# DetectorOptode.net
KiCad netlist of a schematic drawn in Altium Designer
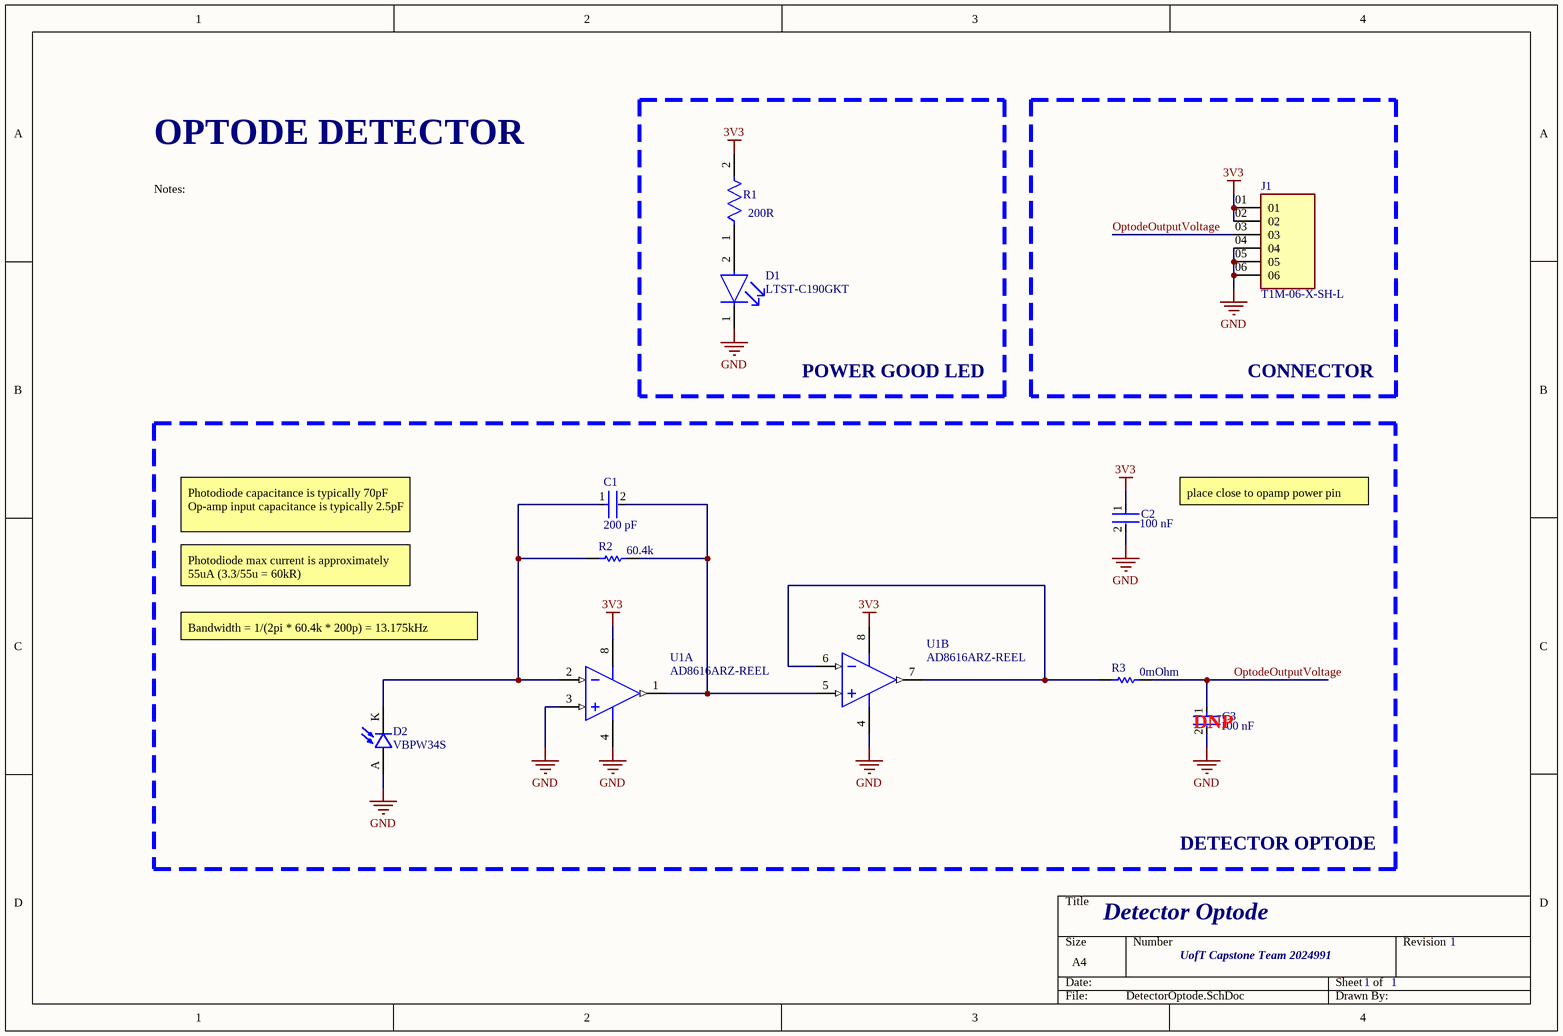
[diagram p0: DetectorOptode.SchDoc]

(export (version "E")
  (design (tool "Eeschema 10.0.6"))
  (components
    (comp (ref "C1")
      (value "C0603C201J5GACTU")
      (footprint "FP-C0603C-CF-MFG")
      (description "CAP CER 200PF 50V 5% NP0 0603")
      (fields
        (field (name "CAPACITANCE") "200 pF")
        (field (name "MANUFACTURER") "KEMET")
        (field (name "OCTOPART") "https://octopart.com/c0603c201j5gactu-kemet-9143917")
      )
      (libsource (lib "Altium Content Vault") (part "b4654b650e69147ec39a6b967a45e02"))
    )
    (comp (ref "C2")
      (value "CC0603KRX7R7BB104")
      (footprint "FP-CC0603-DA-MFG")
      (description "CAP CER 0.1UF 16V X7R 0603")
      (fields
        (field (name "OCTOPART") "https://octopart.com/cc0603krx7r7bb104-yageo-192941")
        (field (name "TOLERANCE") "0.1")
        (field (name "CAPACITANCE") "100 nF")
      )
      (libsource (lib "Altium Content Vault") (part "11868f565c42a9108669ba33697ecf6"))
    )
    (comp (ref "C3")
      (value "CC0603KRX7R7BB104")
      (footprint "FP-CC0603-DA-MFG")
      (description "CAP CER 0.1UF 16V X7R 0603")
      (fields
        (field (name "OCTOPART") "https://octopart.com/cc0603krx7r7bb104-yageo-192941")
        (field (name "TOLERANCE") "0.1")
        (field (name "CAPACITANCE") "100 nF")
      )
      (libsource (lib "Altium Content Vault") (part "11868f565c42a9108669ba33697ecf6"))
    )
    (comp (ref "D1")
      (value "LTST-C190GKT")
      (footprint "FP-LTST-C190GKT-MFG")
      (description "LED GREEN CLEAR CHIP SMD")
      (fields (field (name "VOLTAGE") "2V"))
      (libsource (lib "Altium Content Vault") (part "8706943c75ba83719d021d2fdc84c58"))
    )
    (comp (ref "D2")
      (value "VBPW34S")
      (footprint "PcbLib1:XDCR_VBPW34S")
      (description "Photodiode 940nm 100ns 130Â° 2-SMD, Gull Wing")
      (fields (field (name "MF") "Vishay"))
      (libsource (lib "SourceOptode") (part "VBPW34S"))
    )
    (comp (ref "J1")
      (value "T1M-06-X-SH-L")
      (footprint "SAMTEC_T1M-06-X-SH-L")
      (description "Connector Header Surface Mount, Right Angle 6 position 0.039\" (1.00mm)")
      (fields (field (name "MF") "Samtec"))
      (libsource (lib "DetectorOptode") (part "T1M-06-X-SH-L"))
    )
    (comp (ref "R1")
      (value "CRCW0603200RFKEA")
      (footprint "FP-CRCW0603-e3-MFG")
      (description "RES Thick Film, 200Ω, 1%, 0.1W, 100ppm/°C, 0603")
      (fields (field (name "TOLERANCE") "1%") (field (name "RESISTANCE") "200R"))
      (libsource (lib "Altium Content Vault") (part "1029c3af85768c4190bb7ad29bc67b5"))
    )
    (comp (ref "R2")
      (value "RC0603FR-0760K4L")
      (footprint "RESC1608X55X25ML10T15")
      (fields (field (name "MANUFACTURER") "Yageo") (field (name "RESISTANCE") "60.4k"))
      (libsource (lib "Altium Content Vault") (part "RES"))
    )
    (comp (ref "R3")
      (value "RC0603JR-070RL")
      (footprint "RESC1608X55X25ML10T15")
      (description "Chip Resistor, 0 Ohm, +/- 5%, 0.1 W, -55 to 155 degC, 0603 (1608 Metric), RoHS, Tape and Reel")
      (fields
        (field (name "TOLERANCE") "5%")
        (field (name "RESISTANCE") "0mOhm")
        (field (name "MANUFACTURER") "Yageo")
      )
      (libsource (lib "Altium Content Vault") (part "RES-2"))
    )
    (comp (ref "U1")
      (value "AD8616ARZ-REEL")
      (footprint "ADI-R-8_N")
      (fields (field (name "MANUFACTURER") "Analog Devices") (field (name "GENERIC PART NUMBER") "AD8616"))
      (libsource (lib "Altium Content Vault") (part "ADI-OP29X-R-8"))
    )
  )
  (nets
    (net (code "1") (name "/OptodeOutputVoltage") (class "Default")
      (node (ref "C3") (pin "1") (pinfunction "1_1") (pintype "passive"))
      (node (ref "J1") (pin "03") (pinfunction "03_03") (pintype "passive"))
      (node (ref "R3") (pin "2") (pinfunction "2_2") (pintype "passive"))
    )
    (net (code "2") (name "3V3") (class "Default")
      (node (ref "C2") (pin "1") (pinfunction "1_1") (pintype "passive"))
      (node (ref "J1") (pin "01") (pinfunction "01_01") (pintype "passive"))
      (node (ref "J1") (pin "02") (pinfunction "02_02") (pintype "passive"))
      (node (ref "R1") (pin "2") (pinfunction "2_2") (pintype "passive"))
      (node (ref "U1") (pin "8") (pinfunction "+V_8") (pintype "power_in"))
    )
    (net (code "3") (name "GND") (class "Default")
      (node (ref "C2") (pin "2") (pinfunction "2_2") (pintype "passive"))
      (node (ref "C3") (pin "2") (pinfunction "2_2") (pintype "passive"))
      (node (ref "D1") (pin "1") (pinfunction "C_1") (pintype "passive"))
      (node (ref "D2") (pin "A") (pinfunction "A_A") (pintype "passive"))
      (node (ref "J1") (pin "04") (pinfunction "04_04") (pintype "passive"))
      (node (ref "J1") (pin "05") (pinfunction "05_05") (pintype "passive"))
      (node (ref "J1") (pin "06") (pinfunction "06_06") (pintype "passive"))
      (node (ref "U1") (pin "3") (pinfunction "+IN_A_3") (pintype "input"))
      (node (ref "U1") (pin "4") (pinfunction "-V_4") (pintype "power_in"))
    )
    (net (code "4") (name "Net-(D1-A)") (class "Default")
      (node (ref "D1") (pin "2") (pinfunction "A_2") (pintype "passive"))
      (node (ref "R1") (pin "1") (pinfunction "1_1") (pintype "passive"))
    )
    (net (code "5") (name "Net-(D2-C)") (class "Default")
      (node (ref "C1") (pin "1") (pinfunction "1_1") (pintype "passive"))
      (node (ref "D2") (pin "K") (pinfunction "C_K") (pintype "passive"))
      (node (ref "R2") (pin "1") (pinfunction "1_1") (pintype "passive"))
      (node (ref "U1") (pin "2") (pinfunction "-IN_A_2") (pintype "input"))
    )
    (net (code "6") (name "Net-(U1A-OUT_A)") (class "Default")
      (node (ref "C1") (pin "2") (pinfunction "2_2") (pintype "passive"))
      (node (ref "R2") (pin "2") (pinfunction "2_2") (pintype "passive"))
      (node (ref "U1") (pin "1") (pinfunction "OUT_A_1") (pintype "output"))
      (node (ref "U1") (pin "5") (pinfunction "+IN_B_5") (pintype "input"))
    )
    (net (code "7") (name "Net-(U1B--IN_B)") (class "Default")
      (node (ref "R3") (pin "1") (pinfunction "1_1") (pintype "passive"))
      (node (ref "U1") (pin "6") (pinfunction "-IN_B_6") (pintype "input"))
      (node (ref "U1") (pin "7") (pinfunction "OUT_B_7") (pintype "output"))
    )
  )
)
